# PS2_concentrate.net
KiCad netlist of a schematic drawn in EAGLE
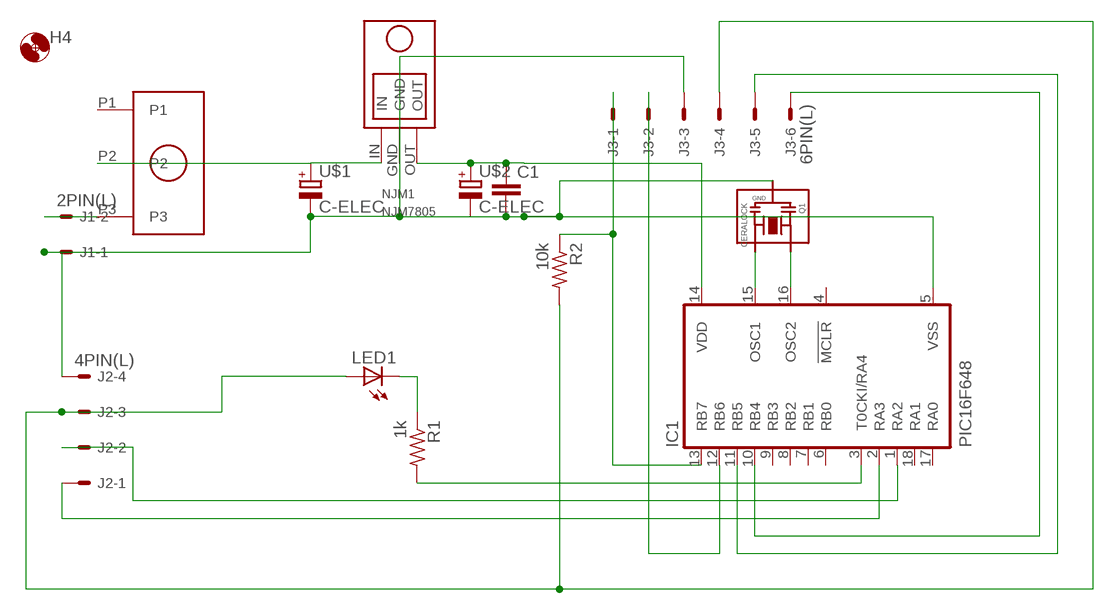
[diagram p0: schematic, sheet 1]

(export (version "E")
  (design (tool "Eeschema 10.0.6"))
  (components
    (comp (ref "C1")
      (value "C-")
      (footprint "eagle-import:C-2.54")
      (libsource (lib "eagle-import") (part "C-"))
    )
    (comp (ref "H4")
      (value "HOLE3.3M3BOLT")
      (footprint "eagle-import:HOLE3.3")
      (libsource (lib "eagle-import") (part "HOLE3.3M3BOLT"))
    )
    (comp (ref "IC1")
      (value "PIC16F648")
      (footprint "eagle-import:DIL18")
      (libsource (lib "eagle-import") (part "PIC16F648"))
    )
    (comp (ref "J1")
      (value "2PIN(L)")
      (footprint "eagle-import:2PL")
      (libsource (lib "eagle-import") (part "2PIN(L)"))
    )
    (comp (ref "J2")
      (value "4PIN(L)")
      (footprint "eagle-import:4PL")
      (libsource (lib "eagle-import") (part "4PIN(L)"))
    )
    (comp (ref "J3")
      (value "6PIN(L)")
      (footprint "eagle-import:6PL")
      (libsource (lib "eagle-import") (part "6PIN(L)"))
    )
    (comp (ref "LED1")
      (value "LED")
      (footprint "eagle-import:LED5MM")
      (libsource (lib "eagle-import") (part "LED"))
    )
    (comp (ref "NJM1")
      (value "NJM7805")
      (footprint "eagle-import:NJM7805")
      (libsource (lib "eagle-import") (part "NJM7805"))
    )
    (comp (ref "Q1")
      (value "CERALOCK")
      (footprint "eagle-import:CERALOCK")
      (libsource (lib "eagle-import") (part "CERALOCK"))
    )
    (comp (ref "R1")
      (value "1k")
      (footprint "eagle-import:0207_10")
      (libsource (lib "eagle-import") (part "R-"))
    )
    (comp (ref "R2")
      (value "10k")
      (footprint "eagle-import:0207_10")
      (libsource (lib "eagle-import") (part "R-"))
    )
    (comp (ref "U$1")
      (value "C-ELEC")
      (footprint "eagle-import:C-6MM")
      (libsource (lib "eagle-import") (part "C-ELEC"))
    )
    (comp (ref "U$2")
      (value "C-ELEC")
      (footprint "eagle-import:C-6MM")
      (libsource (lib "eagle-import") (part "C-ELEC"))
    )
    (comp (ref "U$3")
      (value "TOGGLE_SEITCH")
      (footprint "eagle-import:TOGGLE_SWITCH")
      (libsource (lib "eagle-import") (part "TOGGLE_SEITCH"))
    )
  )
  (nets
    (net (code "1") (name "/5V") (class "Default")
      (node (ref "C1") (pin "P$1") (pinfunction "1_P$1") (pintype "passive"))
      (node (ref "IC1") (pin "14") (pinfunction "VDD_14") (pintype "power_in"))
      (node (ref "J2") (pin "3") (pinfunction "S_3") (pintype "passive"))
      (node (ref "J3") (pin "4") (pinfunction "S_4") (pintype "passive"))
      (node (ref "LED1") (pin "A") (pinfunction "A_A") (pintype "passive"))
      (node (ref "NJM1") (pin "OUT") (pinfunction "OUT_OUT") (pintype "bidirectional"))
      (node (ref "R2") (pin "2") (pinfunction "2_2") (pintype "passive"))
      (node (ref "U$2") (pin "+") (pinfunction "+_+") (pintype "passive"))
    )
    (net (code "2") (name "Net-(C1-2)") (class "Default")
      (node (ref "C1") (pin "P$2") (pinfunction "2_P$2") (pintype "passive"))
      (node (ref "IC1") (pin "5") (pinfunction "VSS_5") (pintype "power_in"))
      (node (ref "J1") (pin "1") (pinfunction "S_1") (pintype "passive"))
      (node (ref "J2") (pin "4") (pinfunction "S_4") (pintype "passive"))
      (node (ref "J3") (pin "3") (pinfunction "S_3") (pintype "passive"))
      (node (ref "NJM1") (pin "GND") (pinfunction "GND_GND") (pintype "bidirectional"))
      (node (ref "Q1") (pin "P$2") (pinfunction "P$2_P$2") (pintype "passive"))
      (node (ref "U$1") (pin "-") (pinfunction "-_-") (pintype "passive"))
      (node (ref "U$2") (pin "-") (pinfunction "-_-") (pintype "passive"))
    )
    (net (code "3") (name "Net-(IC1-OSC1)") (class "Default")
      (node (ref "IC1") (pin "15") (pinfunction "OSC1_15") (pintype "input"))
      (node (ref "Q1") (pin "P$3") (pinfunction "P$3_P$3") (pintype "passive"))
    )
    (net (code "4") (name "Net-(IC1-OSC2)") (class "Default")
      (node (ref "IC1") (pin "16") (pinfunction "OSC2_16") (pintype "output"))
      (node (ref "Q1") (pin "P$1") (pinfunction "P$1_P$1") (pintype "passive"))
    )
    (net (code "5") (name "Net-(IC1-RA2)") (class "Default")
      (node (ref "IC1") (pin "1") (pinfunction "RA2_1") (pintype "bidirectional"))
      (node (ref "J2") (pin "2") (pinfunction "S_2") (pintype "passive"))
    )
    (net (code "6") (name "Net-(IC1-RA3)") (class "Default")
      (node (ref "IC1") (pin "2") (pinfunction "RA3_2") (pintype "bidirectional"))
      (node (ref "J2") (pin "1") (pinfunction "S_1") (pintype "passive"))
    )
    (net (code "7") (name "Net-(IC1-RB4)") (class "Default")
      (node (ref "IC1") (pin "10") (pinfunction "RB4_10") (pintype "bidirectional"))
      (node (ref "J3") (pin "6") (pinfunction "S_6") (pintype "passive"))
    )
    (net (code "8") (name "Net-(IC1-RB5)") (class "Default")
      (node (ref "IC1") (pin "11") (pinfunction "RB5_11") (pintype "bidirectional"))
      (node (ref "J3") (pin "5") (pinfunction "S_5") (pintype "passive"))
    )
    (net (code "9") (name "Net-(IC1-RB6)") (class "Default")
      (node (ref "IC1") (pin "12") (pinfunction "RB6_12") (pintype "bidirectional"))
      (node (ref "J3") (pin "2") (pinfunction "S_2") (pintype "passive"))
    )
    (net (code "10") (name "Net-(IC1-RB7)") (class "Default")
      (node (ref "IC1") (pin "13") (pinfunction "RB7_13") (pintype "bidirectional"))
      (node (ref "J3") (pin "1") (pinfunction "S_1") (pintype "passive"))
      (node (ref "R2") (pin "1") (pinfunction "1_1") (pintype "passive"))
    )
    (net (code "11") (name "Net-(IC1-T0CKI{slash}RA4)") (class "Default")
      (node (ref "IC1") (pin "3") (pinfunction "T0CKI/RA4_3") (pintype "bidirectional"))
      (node (ref "R1") (pin "2") (pinfunction "2_2") (pintype "passive"))
    )
    (net (code "12") (name "Net-(J1B-S)") (class "Default")
      (node (ref "J1") (pin "2") (pinfunction "S_2") (pintype "passive"))
      (node (ref "U$3") (pin "P3") (pinfunction "P3_P3") (pintype "bidirectional"))
    )
    (net (code "13") (name "Net-(LED1-C)") (class "Default")
      (node (ref "LED1") (pin "K") (pinfunction "C_K") (pintype "passive"))
      (node (ref "R1") (pin "1") (pinfunction "1_1") (pintype "passive"))
    )
    (net (code "14") (name "Net-(NJM1-PadIN)") (class "Default")
      (node (ref "NJM1") (pin "IN") (pinfunction "IN_IN") (pintype "bidirectional"))
      (node (ref "U$1") (pin "+") (pinfunction "+_+") (pintype "passive"))
      (node (ref "U$3") (pin "P2") (pinfunction "P2_P2") (pintype "bidirectional"))
    )
    (net (code "15") (name "unconnected-(IC1-RA0-Pad17)") (class "Default")
      (node (ref "IC1") (pin "17") (pinfunction "RA0_17") (pintype "bidirectional"))
    )
    (net (code "16") (name "unconnected-(IC1-RA1-Pad18)") (class "Default")
      (node (ref "IC1") (pin "18") (pinfunction "RA1_18") (pintype "bidirectional"))
    )
    (net (code "17") (name "unconnected-(IC1-RB0-Pad6)") (class "Default")
      (node (ref "IC1") (pin "6") (pinfunction "RB0_6") (pintype "bidirectional"))
    )
    (net (code "18") (name "unconnected-(IC1-RB1-Pad7)") (class "Default")
      (node (ref "IC1") (pin "7") (pinfunction "RB1_7") (pintype "bidirectional"))
    )
    (net (code "19") (name "unconnected-(IC1-RB2-Pad8)") (class "Default")
      (node (ref "IC1") (pin "8") (pinfunction "RB2_8") (pintype "bidirectional"))
    )
    (net (code "20") (name "unconnected-(IC1-RB3-Pad9)") (class "Default")
      (node (ref "IC1") (pin "9") (pinfunction "RB3_9") (pintype "bidirectional"))
    )
    (net (code "21") (name "unconnected-(IC1-~{MCLR}-Pad4)") (class "Default")
      (node (ref "IC1") (pin "4") (pinfunction "~{MCLR}_4") (pintype "input"))
    )
    (net (code "22") (name "unconnected-(U$3-PadP1)") (class "Default")
      (node (ref "U$3") (pin "P1") (pinfunction "P1_P1") (pintype "bidirectional"))
    )
  )
)
